# SinCos.net
KiCad netlist of a schematic drawn in Altium Designer
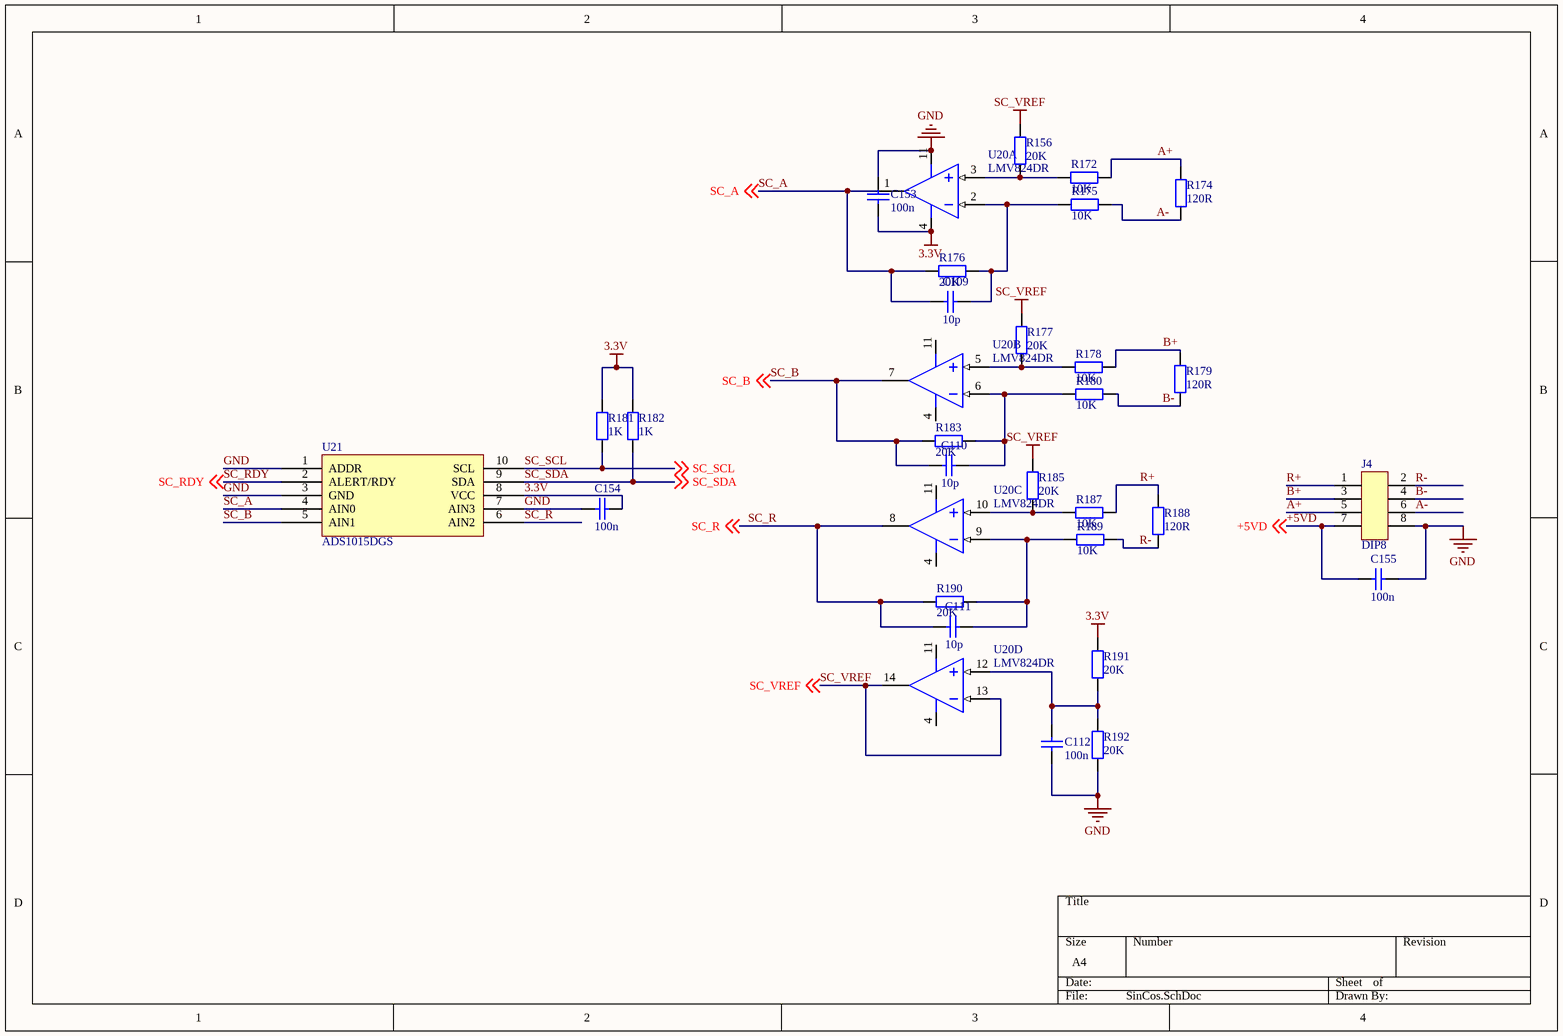
[diagram p0: SinCos.SchDoc]

(export (version "E")
  (design (tool "Eeschema 10.0.6"))
  (components
    (comp (ref "C109")
      (value "10p")
      (footprint "0603C")
      (description "Capacitor")
      (fields (field (name "PUBLISHER") "Altium Limited"))
      (libsource (lib "Main_C") (part "Cap"))
    )
    (comp (ref "C110")
      (value "10p")
      (footprint "0603C")
      (description "Capacitor")
      (fields (field (name "PUBLISHER") "Altium Limited"))
      (libsource (lib "Main_C") (part "Cap"))
    )
    (comp (ref "C111")
      (value "10p")
      (footprint "0603C")
      (description "Capacitor")
      (fields (field (name "PUBLISHER") "Altium Limited"))
      (libsource (lib "Main_C") (part "Cap"))
    )
    (comp (ref "C112")
      (value "100n")
      (footprint "0603C")
      (description "Capacitor")
      (fields (field (name "PUBLISHER") "Altium Limited"))
      (libsource (lib "Main_C") (part "Cap"))
    )
    (comp (ref "C153")
      (value "100n")
      (footprint "0603C")
      (description "Capacitor")
      (fields (field (name "PUBLISHER") "Altium Limited"))
      (libsource (lib "Main_C") (part "Cap"))
    )
    (comp (ref "C154")
      (value "100n")
      (footprint "0603C")
      (description "Capacitor")
      (fields (field (name "PUBLISHER") "Altium Limited"))
      (libsource (lib "Main_C") (part "Cap"))
    )
    (comp (ref "C155")
      (value "100n")
      (footprint "0603C")
      (description "Capacitor")
      (fields (field (name "PUBLISHER") "Altium Limited"))
      (libsource (lib "Main_C") (part "Cap"))
    )
    (comp (ref "J4")
      (value "DIP8")
      (footprint "DIP8-2.54")
      (description "Connectors")
      (fields (field (name "PUBLISHER") "Altium Limited"))
      (libsource (lib "jointbar") (part "DIP8"))
    )
    (comp (ref "R156")
      (value "20K")
      (footprint "0603R")
      (description "Resistor")
      (fields (field (name "PUBLISHER") "Altium Limited"))
      (libsource (lib "Main_C") (part "Res2"))
    )
    (comp (ref "R172")
      (value "10K")
      (footprint "0603R")
      (description "Resistor")
      (fields (field (name "PUBLISHER") "Altium Limited"))
      (libsource (lib "") (part "Res2_1"))
    )
    (comp (ref "R174")
      (value "120R")
      (footprint "0603R")
      (description "Resistor")
      (fields (field (name "PUBLISHER") "Altium Limited"))
      (libsource (lib "Main_C") (part "Res2"))
    )
    (comp (ref "R175")
      (value "10K")
      (footprint "0603R")
      (description "Resistor")
      (fields (field (name "PUBLISHER") "Altium Limited"))
      (libsource (lib "") (part "Res2_1"))
    )
    (comp (ref "R176")
      (value "20K")
      (footprint "0603R")
      (description "Resistor")
      (fields (field (name "PUBLISHER") "Altium Limited"))
      (libsource (lib "") (part "Res2_2"))
    )
    (comp (ref "R177")
      (value "20K")
      (footprint "0603R")
      (description "Resistor")
      (fields (field (name "PUBLISHER") "Altium Limited"))
      (libsource (lib "Main_C") (part "Res2"))
    )
    (comp (ref "R178")
      (value "10K")
      (footprint "0603R")
      (description "Resistor")
      (fields (field (name "PUBLISHER") "Altium Limited"))
      (libsource (lib "") (part "Res2_1"))
    )
    (comp (ref "R179")
      (value "120R")
      (footprint "0603R")
      (description "Resistor")
      (fields (field (name "PUBLISHER") "Altium Limited"))
      (libsource (lib "Main_C") (part "Res2"))
    )
    (comp (ref "R180")
      (value "10K")
      (footprint "0603R")
      (description "Resistor")
      (fields (field (name "PUBLISHER") "Altium Limited"))
      (libsource (lib "") (part "Res2_1"))
    )
    (comp (ref "R181")
      (value "1K")
      (footprint "0603R")
      (description "Resistor")
      (fields (field (name "PUBLISHER") "Altium Limited"))
      (libsource (lib "Main_C") (part "Res2"))
    )
    (comp (ref "R182")
      (value "1K")
      (footprint "0603R")
      (description "Resistor")
      (fields (field (name "PUBLISHER") "Altium Limited"))
      (libsource (lib "Main_C") (part "Res2"))
    )
    (comp (ref "R183")
      (value "20K")
      (footprint "0603R")
      (description "Resistor")
      (fields (field (name "PUBLISHER") "Altium Limited"))
      (libsource (lib "") (part "Res2_2"))
    )
    (comp (ref "R185")
      (value "20K")
      (footprint "0603R")
      (description "Resistor")
      (fields (field (name "PUBLISHER") "Altium Limited"))
      (libsource (lib "Main_C") (part "Res2"))
    )
    (comp (ref "R187")
      (value "10K")
      (footprint "0603R")
      (description "Resistor")
      (fields (field (name "PUBLISHER") "Altium Limited"))
      (libsource (lib "") (part "Res2_1"))
    )
    (comp (ref "R188")
      (value "120R")
      (footprint "0603R")
      (description "Resistor")
      (fields (field (name "PUBLISHER") "Altium Limited"))
      (libsource (lib "Main_C") (part "Res2"))
    )
    (comp (ref "R189")
      (value "10K")
      (footprint "0603R")
      (description "Resistor")
      (fields (field (name "PUBLISHER") "Altium Limited"))
      (libsource (lib "") (part "Res2_1"))
    )
    (comp (ref "R190")
      (value "20K")
      (footprint "0603R")
      (description "Resistor")
      (fields (field (name "PUBLISHER") "Altium Limited"))
      (libsource (lib "") (part "Res2_2"))
    )
    (comp (ref "R191")
      (value "20K")
      (footprint "0603R")
      (description "Resistor")
      (fields (field (name "PUBLISHER") "Altium Limited"))
      (libsource (lib "Main_C") (part "Res2"))
    )
    (comp (ref "R192")
      (value "20K")
      (footprint "0603R")
      (description "Resistor")
      (fields (field (name "PUBLISHER") "Altium Limited"))
      (libsource (lib "Main_C") (part "Res2"))
    )
    (comp (ref "U20")
      (value "LMV824DR")
      (footprint "SOP-14")
      (description "Quad Single-Supply Comparator")
      (fields (field (name "PUBLISHER") "Altium Limited"))
      (libsource (lib "Main_C") (part "LM339AD"))
    )
    (comp (ref "U21") (value "ADS1015DGS") (footprint "VSSOP-10") (libsource (lib "Main_C") (part "ADS1015")))
  )
  (nets
    (net (code "1") (name "+5VD") (class "Default")
      (node (ref "C155") (pin "2") (pinfunction "2_2") (pintype "passive"))
      (node (ref "J4") (pin "7") (pinfunction "7_7") (pintype "passive"))
    )
    (net (code "2") (name "/A+") (class "Default")
      (node (ref "J4") (pin "5") (pinfunction "5_5") (pintype "passive"))
      (node (ref "R172") (pin "1") (pinfunction "1_1") (pintype "passive"))
      (node (ref "R174") (pin "1") (pinfunction "1_1") (pintype "passive"))
    )
    (net (code "3") (name "/A-") (class "Default")
      (node (ref "J4") (pin "6") (pinfunction "6_6") (pintype "passive"))
      (node (ref "R174") (pin "2") (pinfunction "2_2") (pintype "passive"))
      (node (ref "R175") (pin "1") (pinfunction "1_1") (pintype "passive"))
    )
    (net (code "4") (name "/B+") (class "Default")
      (node (ref "J4") (pin "3") (pinfunction "3_3") (pintype "passive"))
      (node (ref "R178") (pin "1") (pinfunction "1_1") (pintype "passive"))
      (node (ref "R179") (pin "1") (pinfunction "1_1") (pintype "passive"))
    )
    (net (code "5") (name "/B-") (class "Default")
      (node (ref "J4") (pin "4") (pinfunction "4_4") (pintype "passive"))
      (node (ref "R179") (pin "2") (pinfunction "2_2") (pintype "passive"))
      (node (ref "R180") (pin "1") (pinfunction "1_1") (pintype "passive"))
    )
    (net (code "6") (name "/R+") (class "Default")
      (node (ref "J4") (pin "1") (pinfunction "1_1") (pintype "passive"))
      (node (ref "R187") (pin "1") (pinfunction "1_1") (pintype "passive"))
      (node (ref "R188") (pin "1") (pinfunction "1_1") (pintype "passive"))
    )
    (net (code "7") (name "/R-") (class "Default")
      (node (ref "J4") (pin "2") (pinfunction "2_2") (pintype "passive"))
      (node (ref "R188") (pin "2") (pinfunction "2_2") (pintype "passive"))
      (node (ref "R189") (pin "1") (pinfunction "1_1") (pintype "passive"))
    )
    (net (code "8") (name "3.3V") (class "Default")
      (node (ref "C153") (pin "1") (pinfunction "1_1") (pintype "passive"))
      (node (ref "C154") (pin "1") (pinfunction "1_1") (pintype "passive"))
      (node (ref "R181") (pin "1") (pinfunction "1_1") (pintype "passive"))
      (node (ref "R182") (pin "1") (pinfunction "1_1") (pintype "passive"))
      (node (ref "R191") (pin "1") (pinfunction "1_1") (pintype "passive"))
      (node (ref "U20") (pin "4") (pinfunction "GND_4") (pintype "power_in"))
      (node (ref "U21") (pin "8") (pinfunction "VCC_8") (pintype "passive"))
    )
    (net (code "9") (name "GND") (class "Default")
      (node (ref "C112") (pin "1") (pinfunction "1_1") (pintype "passive"))
      (node (ref "C153") (pin "2") (pinfunction "2_2") (pintype "passive"))
      (node (ref "C154") (pin "2") (pinfunction "2_2") (pintype "passive"))
      (node (ref "C155") (pin "1") (pinfunction "1_1") (pintype "passive"))
      (node (ref "J4") (pin "8") (pinfunction "8_8") (pintype "passive"))
      (node (ref "R192") (pin "2") (pinfunction "2_2") (pintype "passive"))
      (node (ref "U20") (pin "11") (pinfunction "V+_11") (pintype "power_in"))
      (node (ref "U21") (pin "1") (pinfunction "ADDR_1") (pintype "passive"))
      (node (ref "U21") (pin "3") (pinfunction "GND_3") (pintype "passive"))
      (node (ref "U21") (pin "7") (pinfunction "AIN3_7") (pintype "passive"))
    )
    (net (code "10") (name "Net-(U20A-IN+)") (class "Default")
      (node (ref "R156") (pin "2") (pinfunction "2_2") (pintype "passive"))
      (node (ref "R172") (pin "2") (pinfunction "2_2") (pintype "passive"))
      (node (ref "U20") (pin "3") (pinfunction "IN+_3") (pintype "input"))
    )
    (net (code "11") (name "Net-(U20A-IN-)") (class "Default")
      (node (ref "C109") (pin "2") (pinfunction "2_2") (pintype "passive"))
      (node (ref "R175") (pin "2") (pinfunction "2_2") (pintype "passive"))
      (node (ref "R176") (pin "2") (pinfunction "2_2") (pintype "passive"))
      (node (ref "U20") (pin "2") (pinfunction "IN-_2") (pintype "input"))
    )
    (net (code "12") (name "Net-(U20B-IN+)") (class "Default")
      (node (ref "R177") (pin "2") (pinfunction "2_2") (pintype "passive"))
      (node (ref "R178") (pin "2") (pinfunction "2_2") (pintype "passive"))
      (node (ref "U20") (pin "5") (pinfunction "IN+_5") (pintype "input"))
    )
    (net (code "13") (name "Net-(U20B-IN-)") (class "Default")
      (node (ref "C110") (pin "2") (pinfunction "2_2") (pintype "passive"))
      (node (ref "R180") (pin "2") (pinfunction "2_2") (pintype "passive"))
      (node (ref "R183") (pin "2") (pinfunction "2_2") (pintype "passive"))
      (node (ref "U20") (pin "6") (pinfunction "IN-_6") (pintype "input"))
    )
    (net (code "14") (name "Net-(U20C-IN+)") (class "Default")
      (node (ref "R185") (pin "2") (pinfunction "2_2") (pintype "passive"))
      (node (ref "R187") (pin "2") (pinfunction "2_2") (pintype "passive"))
      (node (ref "U20") (pin "10") (pinfunction "IN+_10") (pintype "input"))
    )
    (net (code "15") (name "Net-(U20C-IN-)") (class "Default")
      (node (ref "C111") (pin "2") (pinfunction "2_2") (pintype "passive"))
      (node (ref "R189") (pin "2") (pinfunction "2_2") (pintype "passive"))
      (node (ref "R190") (pin "2") (pinfunction "2_2") (pintype "passive"))
      (node (ref "U20") (pin "9") (pinfunction "IN-_9") (pintype "input"))
    )
    (net (code "16") (name "Net-(U20D-IN+)") (class "Default")
      (node (ref "C112") (pin "2") (pinfunction "2_2") (pintype "passive"))
      (node (ref "R191") (pin "2") (pinfunction "2_2") (pintype "passive"))
      (node (ref "R192") (pin "1") (pinfunction "1_1") (pintype "passive"))
      (node (ref "U20") (pin "12") (pinfunction "IN+_12") (pintype "input"))
    )
    (net (code "17") (name "SC_A") (class "Default")
      (node (ref "C109") (pin "1") (pinfunction "1_1") (pintype "passive"))
      (node (ref "R176") (pin "1") (pinfunction "1_1") (pintype "passive"))
      (node (ref "U20") (pin "1") (pinfunction "OUT_1") (pintype "open_collector"))
      (node (ref "U21") (pin "4") (pinfunction "AIN0_4") (pintype "passive"))
    )
    (net (code "18") (name "SC_B") (class "Default")
      (node (ref "C110") (pin "1") (pinfunction "1_1") (pintype "passive"))
      (node (ref "R183") (pin "1") (pinfunction "1_1") (pintype "passive"))
      (node (ref "U20") (pin "7") (pinfunction "OUT2_7") (pintype "open_collector"))
      (node (ref "U21") (pin "5") (pinfunction "AIN1_5") (pintype "passive"))
    )
    (net (code "19") (name "SC_R") (class "Default")
      (node (ref "C111") (pin "1") (pinfunction "1_1") (pintype "passive"))
      (node (ref "R190") (pin "1") (pinfunction "1_1") (pintype "passive"))
      (node (ref "U20") (pin "8") (pinfunction "OUT_8") (pintype "open_collector"))
      (node (ref "U21") (pin "6") (pinfunction "AIN2_6") (pintype "passive"))
    )
    (net (code "20") (name "SC_RDY") (class "Default")
      (node (ref "U21") (pin "2") (pinfunction "ALERT/RDY_2") (pintype "passive"))
    )
    (net (code "21") (name "SC_SCL") (class "Default")
      (node (ref "R181") (pin "2") (pinfunction "2_2") (pintype "passive"))
      (node (ref "U21") (pin "10") (pinfunction "SCL_10") (pintype "passive"))
    )
    (net (code "22") (name "SC_SDA") (class "Default")
      (node (ref "R182") (pin "2") (pinfunction "2_2") (pintype "passive"))
      (node (ref "U21") (pin "9") (pinfunction "SDA_9") (pintype "passive"))
    )
    (net (code "23") (name "SC_VREF") (class "Default")
      (node (ref "R156") (pin "1") (pinfunction "1_1") (pintype "passive"))
      (node (ref "R177") (pin "1") (pinfunction "1_1") (pintype "passive"))
      (node (ref "R185") (pin "1") (pinfunction "1_1") (pintype "passive"))
      (node (ref "U20") (pin "13") (pinfunction "IN-_13") (pintype "input"))
      (node (ref "U20") (pin "14") (pinfunction "OUT_14") (pintype "open_collector"))
    )
    (net (code "24") (name "unconnected-(U20B-GND-Pad4)") (class "Default")
      (node (ref "U20") (pin "4") (pinfunction "GND_4") (pintype "power_in"))
    )
    (net (code "25") (name "unconnected-(U20B-V+-Pad11)") (class "Default")
      (node (ref "U20") (pin "11") (pinfunction "V+_11") (pintype "power_in"))
    )
    (net (code "26") (name "unconnected-(U20C-GND-Pad4)") (class "Default")
      (node (ref "U20") (pin "4") (pinfunction "GND_4") (pintype "power_in"))
    )
    (net (code "27") (name "unconnected-(U20C-V+-Pad11)") (class "Default")
      (node (ref "U20") (pin "11") (pinfunction "V+_11") (pintype "power_in"))
    )
    (net (code "28") (name "unconnected-(U20D-GND-Pad4)") (class "Default")
      (node (ref "U20") (pin "4") (pinfunction "GND_4") (pintype "power_in"))
    )
    (net (code "29") (name "unconnected-(U20D-V+-Pad11)") (class "Default")
      (node (ref "U20") (pin "11") (pinfunction "V+_11") (pintype "power_in"))
    )
  )
)
